# dashboard.net
KiCad netlist of a schematic drawn in EAGLE
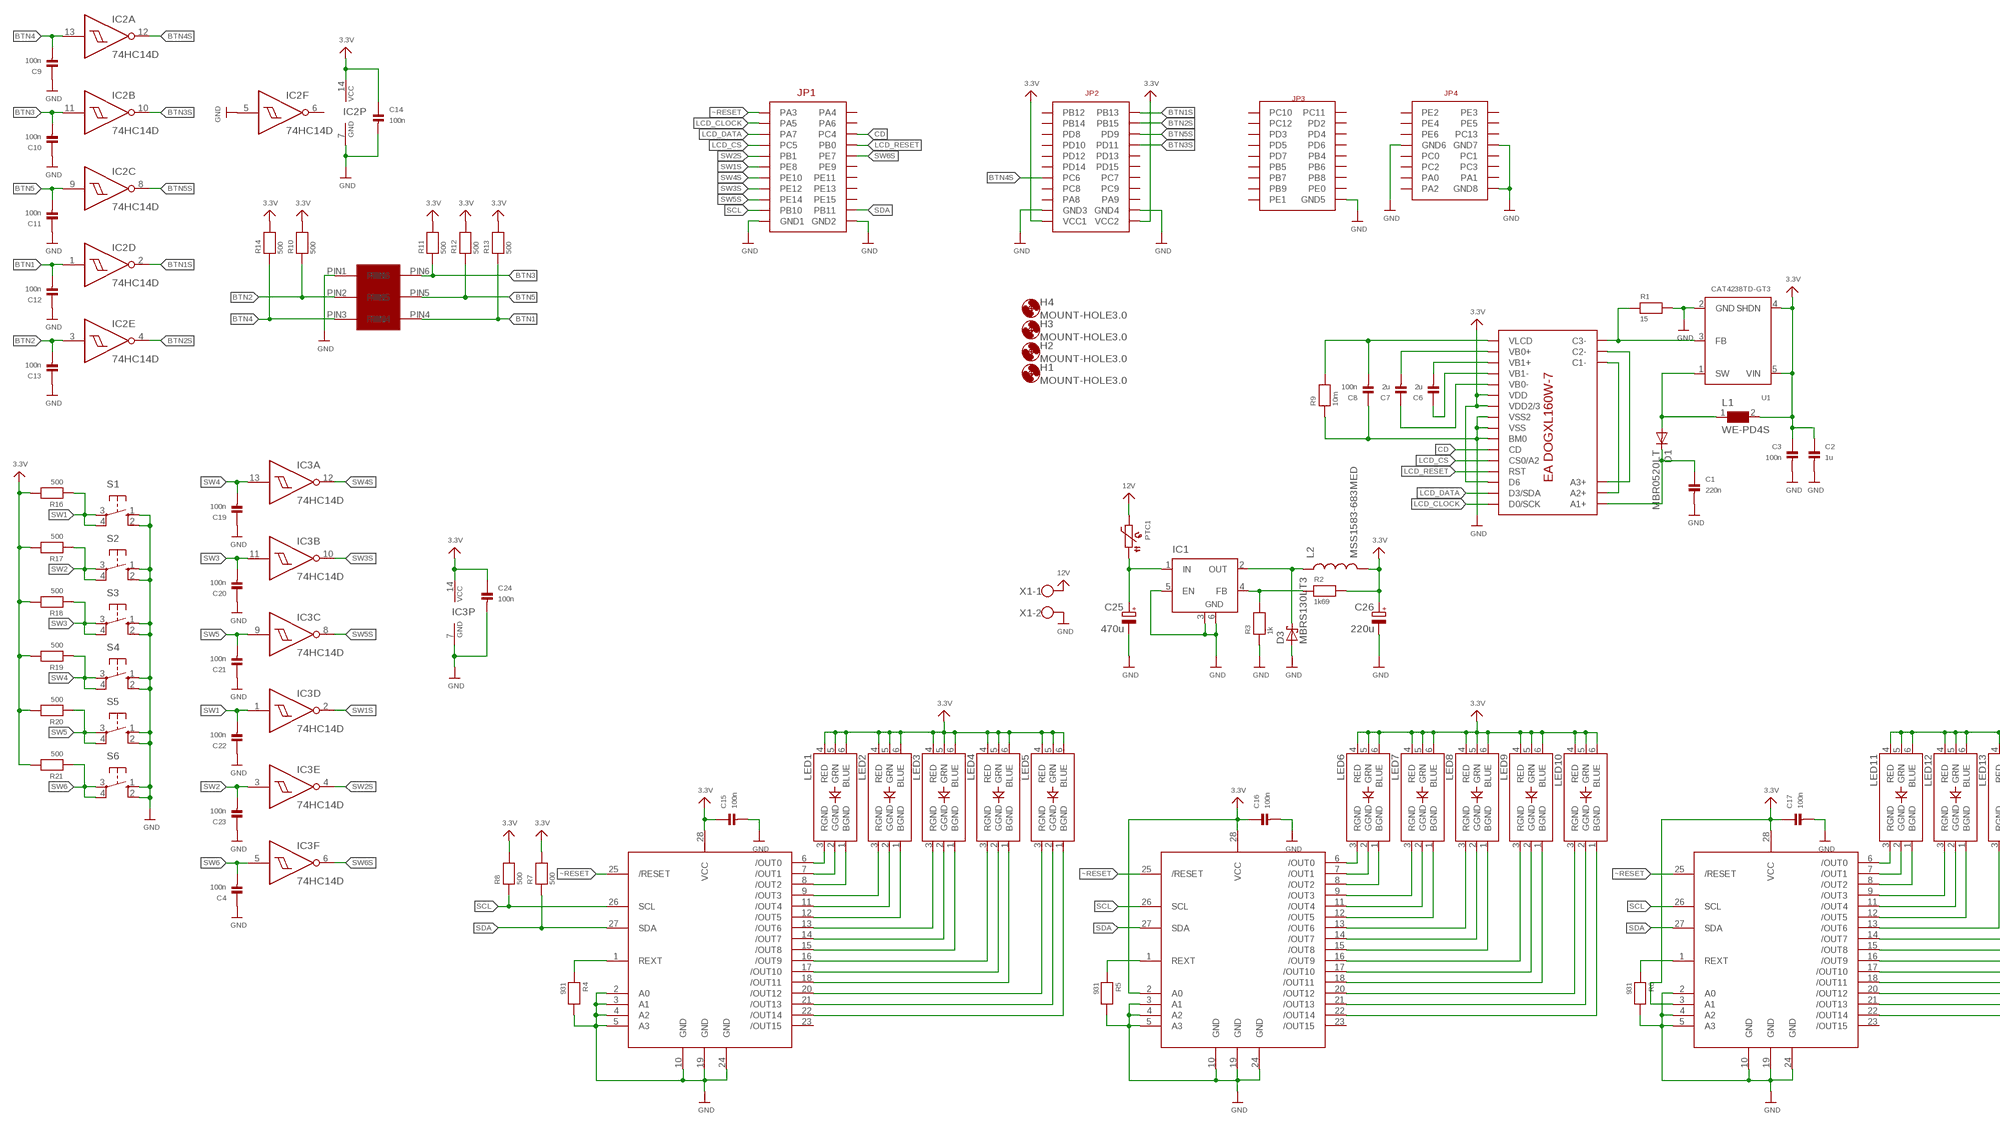
[diagram p0: schematic, sheet 1, part 1 of 2]
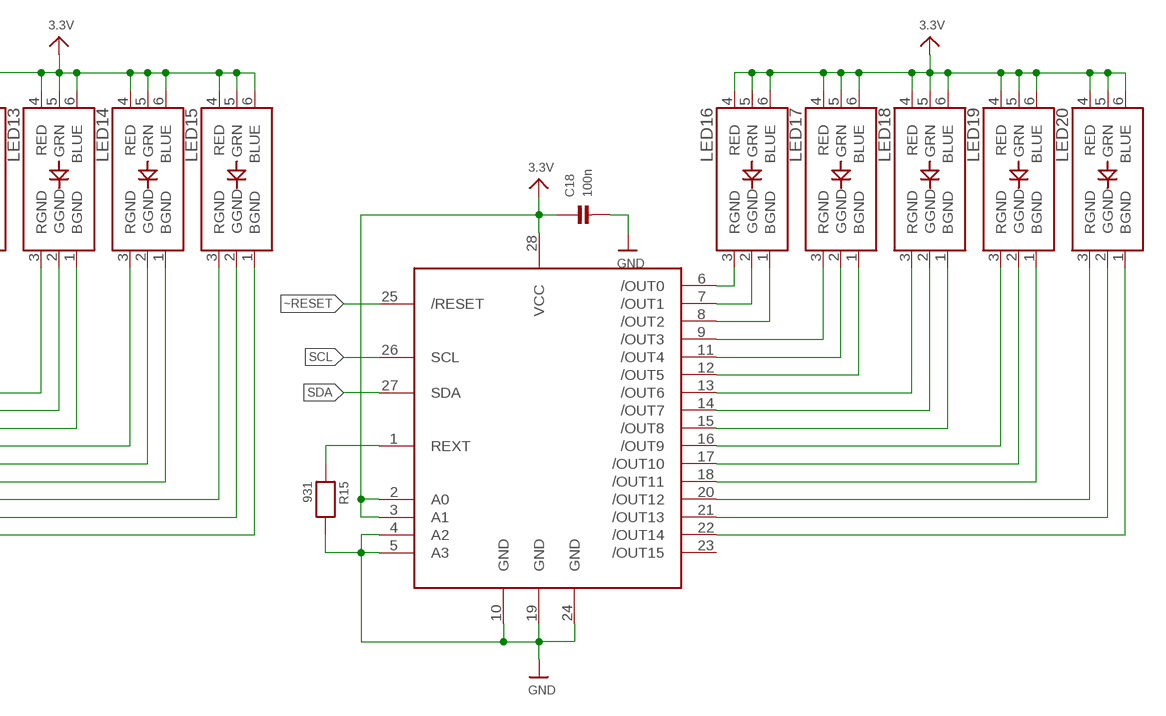
[diagram p1: schematic, sheet 1, part 2 of 2]

(export (version "E")
  (design (tool "Eeschema 10.0.6"))
  (components
    (comp (ref "C1")
      (value "220n")
      (footprint "eagle-import:_0805")
      (libsource (lib "eagle-import") (part "CAP_CERAMIC_0805"))
    )
    (comp (ref "C2")
      (value "1u")
      (footprint "eagle-import:_0805")
      (libsource (lib "eagle-import") (part "CAP_CERAMIC_0805"))
    )
    (comp (ref "C3")
      (value "100n")
      (footprint "eagle-import:_0603")
      (libsource (lib "eagle-import") (part "CAP_CERAMIC_0603"))
    )
    (comp (ref "C4")
      (value "100n")
      (footprint "eagle-import:_0603")
      (libsource (lib "eagle-import") (part "CAP_CERAMIC_0603"))
    )
    (comp (ref "C6")
      (value "2u")
      (footprint "eagle-import:_0805")
      (libsource (lib "eagle-import") (part "CAP_CERAMIC_0805"))
    )
    (comp (ref "C7")
      (value "2u")
      (footprint "eagle-import:_0805")
      (libsource (lib "eagle-import") (part "CAP_CERAMIC_0805"))
    )
    (comp (ref "C8")
      (value "100n")
      (footprint "eagle-import:_0603")
      (libsource (lib "eagle-import") (part "CAP_CERAMIC_0603"))
    )
    (comp (ref "C9")
      (value "100n")
      (footprint "eagle-import:_0603")
      (libsource (lib "eagle-import") (part "CAP_CERAMIC_0603"))
    )
    (comp (ref "C10")
      (value "100n")
      (footprint "eagle-import:_0603")
      (libsource (lib "eagle-import") (part "CAP_CERAMIC_0603"))
    )
    (comp (ref "C11")
      (value "100n")
      (footprint "eagle-import:_0603")
      (libsource (lib "eagle-import") (part "CAP_CERAMIC_0603"))
    )
    (comp (ref "C12")
      (value "100n")
      (footprint "eagle-import:_0603")
      (libsource (lib "eagle-import") (part "CAP_CERAMIC_0603"))
    )
    (comp (ref "C13")
      (value "100n")
      (footprint "eagle-import:_0603")
      (libsource (lib "eagle-import") (part "CAP_CERAMIC_0603"))
    )
    (comp (ref "C14")
      (value "100n")
      (footprint "eagle-import:_0603")
      (libsource (lib "eagle-import") (part "CAP_CERAMIC_0603"))
    )
    (comp (ref "C15")
      (value "100n")
      (footprint "eagle-import:_0603")
      (libsource (lib "eagle-import") (part "CAP_CERAMIC_0603"))
    )
    (comp (ref "C16")
      (value "100n")
      (footprint "eagle-import:_0603")
      (libsource (lib "eagle-import") (part "CAP_CERAMIC_0603"))
    )
    (comp (ref "C17")
      (value "100n")
      (footprint "eagle-import:_0603")
      (libsource (lib "eagle-import") (part "CAP_CERAMIC_0603"))
    )
    (comp (ref "C18")
      (value "100n")
      (footprint "eagle-import:_0603")
      (libsource (lib "eagle-import") (part "CAP_CERAMIC_0603"))
    )
    (comp (ref "C19")
      (value "100n")
      (footprint "eagle-import:_0603")
      (libsource (lib "eagle-import") (part "CAP_CERAMIC_0603"))
    )
    (comp (ref "C20")
      (value "100n")
      (footprint "eagle-import:_0603")
      (libsource (lib "eagle-import") (part "CAP_CERAMIC_0603"))
    )
    (comp (ref "C21")
      (value "100n")
      (footprint "eagle-import:_0603")
      (libsource (lib "eagle-import") (part "CAP_CERAMIC_0603"))
    )
    (comp (ref "C22")
      (value "100n")
      (footprint "eagle-import:_0603")
      (libsource (lib "eagle-import") (part "CAP_CERAMIC_0603"))
    )
    (comp (ref "C23")
      (value "100n")
      (footprint "eagle-import:_0603")
      (libsource (lib "eagle-import") (part "CAP_CERAMIC_0603"))
    )
    (comp (ref "C24")
      (value "100n")
      (footprint "eagle-import:_0603")
      (libsource (lib "eagle-import") (part "CAP_CERAMIC_0603"))
    )
    (comp (ref "C25")
      (value "470u")
      (footprint "eagle-import:153CLV-1012")
      (libsource (lib "eagle-import") (part "CPOL-EU153CLV-1012"))
    )
    (comp (ref "C26")
      (value "220u")
      (footprint "eagle-import:153CLV-1012")
      (libsource (lib "eagle-import") (part "CPOL-EU153CLV-1012"))
    )
    (comp (ref "D1")
      (value "MBR0520LT")
      (footprint "eagle-import:SOD123")
      (libsource (lib "eagle-import") (part "MBR0520LT"))
    )
    (comp (ref "D3")
      (value "MBRS130LT3")
      (footprint "eagle-import:SMB")
      (libsource (lib "eagle-import") (part "MBRS130LT3"))
    )
    (comp (ref "H1")
      (value "MOUNT-HOLE3.0")
      (footprint "eagle-import:3,0")
      (libsource (lib "eagle-import") (part "MOUNT-HOLE3.0"))
    )
    (comp (ref "H2")
      (value "MOUNT-HOLE3.0")
      (footprint "eagle-import:3,0")
      (libsource (lib "eagle-import") (part "MOUNT-HOLE3.0"))
    )
    (comp (ref "H3")
      (value "MOUNT-HOLE3.0")
      (footprint "eagle-import:3,0")
      (libsource (lib "eagle-import") (part "MOUNT-HOLE3.0"))
    )
    (comp (ref "H4")
      (value "MOUNT-HOLE3.0")
      (footprint "eagle-import:3,0")
      (libsource (lib "eagle-import") (part "MOUNT-HOLE3.0"))
    )
    (comp (ref "IC1")
      (value "LM2596S")
      (footprint "eagle-import:TO263-5")
      (libsource (lib "eagle-import") (part "LM2596S"))
    )
    (comp (ref "IC2")
      (value "74HC14D")
      (footprint "eagle-import:SO14")
      (libsource (lib "eagle-import") (part "7414DHC"))
    )
    (comp (ref "IC3")
      (value "74HC14D")
      (footprint "eagle-import:SO14")
      (libsource (lib "eagle-import") (part "7414DHC"))
    )
    (comp (ref "L1")
      (value "WE-PD4S")
      (footprint "eagle-import:S")
      (fields (field (name "MPN") "7445501"))
      (libsource (lib "eagle-import") (part "WE-PD4_S-7445501"))
    )
    (comp (ref "L2")
      (value "MSS1583-683MED")
      (footprint "eagle-import:CDRH125")
      (libsource (lib "eagle-import") (part "INDUCTORPWR"))
    )
    (comp (ref "LED1")
      (value "LED_RGB_PLCC6CREE-CLV6A")
      (footprint "eagle-import:RGBLED_PLCC6")
      (libsource (lib "eagle-import") (part "LED_RGB_PLCC6CREE-CLV6A"))
    )
    (comp (ref "LED2")
      (value "LED_RGB_PLCC6CREE-CLV6A")
      (footprint "eagle-import:RGBLED_PLCC6")
      (libsource (lib "eagle-import") (part "LED_RGB_PLCC6CREE-CLV6A"))
    )
    (comp (ref "LED3")
      (value "LED_RGB_PLCC6CREE-CLV6A")
      (footprint "eagle-import:RGBLED_PLCC6")
      (libsource (lib "eagle-import") (part "LED_RGB_PLCC6CREE-CLV6A"))
    )
    (comp (ref "LED4")
      (value "LED_RGB_PLCC6CREE-CLV6A")
      (footprint "eagle-import:RGBLED_PLCC6")
      (libsource (lib "eagle-import") (part "LED_RGB_PLCC6CREE-CLV6A"))
    )
    (comp (ref "LED5")
      (value "LED_RGB_PLCC6CREE-CLV6A")
      (footprint "eagle-import:RGBLED_PLCC6")
      (libsource (lib "eagle-import") (part "LED_RGB_PLCC6CREE-CLV6A"))
    )
    (comp (ref "LED6")
      (value "LED_RGB_PLCC6CREE-CLV6A")
      (footprint "eagle-import:RGBLED_PLCC6")
      (libsource (lib "eagle-import") (part "LED_RGB_PLCC6CREE-CLV6A"))
    )
    (comp (ref "LED7")
      (value "LED_RGB_PLCC6CREE-CLV6A")
      (footprint "eagle-import:RGBLED_PLCC6")
      (libsource (lib "eagle-import") (part "LED_RGB_PLCC6CREE-CLV6A"))
    )
    (comp (ref "LED8")
      (value "LED_RGB_PLCC6CREE-CLV6A")
      (footprint "eagle-import:RGBLED_PLCC6")
      (libsource (lib "eagle-import") (part "LED_RGB_PLCC6CREE-CLV6A"))
    )
    (comp (ref "LED9")
      (value "LED_RGB_PLCC6CREE-CLV6A")
      (footprint "eagle-import:RGBLED_PLCC6")
      (libsource (lib "eagle-import") (part "LED_RGB_PLCC6CREE-CLV6A"))
    )
    (comp (ref "LED10")
      (value "LED_RGB_PLCC6CREE-CLV6A")
      (footprint "eagle-import:RGBLED_PLCC6")
      (libsource (lib "eagle-import") (part "LED_RGB_PLCC6CREE-CLV6A"))
    )
    (comp (ref "LED11")
      (value "LED_RGB_PLCC6CREE-CLV6A")
      (footprint "eagle-import:RGBLED_PLCC6")
      (libsource (lib "eagle-import") (part "LED_RGB_PLCC6CREE-CLV6A"))
    )
    (comp (ref "LED12")
      (value "LED_RGB_PLCC6CREE-CLV6A")
      (footprint "eagle-import:RGBLED_PLCC6")
      (libsource (lib "eagle-import") (part "LED_RGB_PLCC6CREE-CLV6A"))
    )
    (comp (ref "LED13")
      (value "LED_RGB_PLCC6CREE-CLV6A")
      (footprint "eagle-import:RGBLED_PLCC6")
      (libsource (lib "eagle-import") (part "LED_RGB_PLCC6CREE-CLV6A"))
    )
    (comp (ref "LED14")
      (value "LED_RGB_PLCC6CREE-CLV6A")
      (footprint "eagle-import:RGBLED_PLCC6")
      (libsource (lib "eagle-import") (part "LED_RGB_PLCC6CREE-CLV6A"))
    )
    (comp (ref "LED15")
      (value "LED_RGB_PLCC6CREE-CLV6A")
      (footprint "eagle-import:RGBLED_PLCC6")
      (libsource (lib "eagle-import") (part "LED_RGB_PLCC6CREE-CLV6A"))
    )
    (comp (ref "LED16")
      (value "LED_RGB_PLCC6CREE-CLV6A")
      (footprint "eagle-import:RGBLED_PLCC6")
      (libsource (lib "eagle-import") (part "LED_RGB_PLCC6CREE-CLV6A"))
    )
    (comp (ref "LED17")
      (value "LED_RGB_PLCC6CREE-CLV6A")
      (footprint "eagle-import:RGBLED_PLCC6")
      (libsource (lib "eagle-import") (part "LED_RGB_PLCC6CREE-CLV6A"))
    )
    (comp (ref "LED18")
      (value "LED_RGB_PLCC6CREE-CLV6A")
      (footprint "eagle-import:RGBLED_PLCC6")
      (libsource (lib "eagle-import") (part "LED_RGB_PLCC6CREE-CLV6A"))
    )
    (comp (ref "LED19")
      (value "LED_RGB_PLCC6CREE-CLV6A")
      (footprint "eagle-import:RGBLED_PLCC6")
      (libsource (lib "eagle-import") (part "LED_RGB_PLCC6CREE-CLV6A"))
    )
    (comp (ref "LED20")
      (value "LED_RGB_PLCC6CREE-CLV6A")
      (footprint "eagle-import:RGBLED_PLCC6")
      (libsource (lib "eagle-import") (part "LED_RGB_PLCC6CREE-CLV6A"))
    )
    (comp (ref "PTC1")
      (value "PTC1812")
      (footprint "eagle-import:PTC1812")
      (libsource (lib "eagle-import") (part "PTC1812"))
    )
    (comp (ref "R1")
      (value "15")
      (footprint "eagle-import:_0603")
      (libsource (lib "eagle-import") (part "RESISTOR_0603"))
    )
    (comp (ref "R2")
      (value "1k69")
      (footprint "eagle-import:_0603")
      (libsource (lib "eagle-import") (part "RESISTOR_0603"))
    )
    (comp (ref "R3")
      (value "1k")
      (footprint "eagle-import:_0603")
      (libsource (lib "eagle-import") (part "RESISTOR_0603"))
    )
    (comp (ref "R4")
      (value "931")
      (footprint "eagle-import:_0603")
      (libsource (lib "eagle-import") (part "RESISTOR_0603"))
    )
    (comp (ref "R5")
      (value "931")
      (footprint "eagle-import:_0603")
      (libsource (lib "eagle-import") (part "RESISTOR_0603"))
    )
    (comp (ref "R6")
      (value "931")
      (footprint "eagle-import:_0603")
      (libsource (lib "eagle-import") (part "RESISTOR_0603"))
    )
    (comp (ref "R7")
      (value "500")
      (footprint "eagle-import:_0603")
      (libsource (lib "eagle-import") (part "RESISTOR_0603"))
    )
    (comp (ref "R8")
      (value "500")
      (footprint "eagle-import:_0603")
      (libsource (lib "eagle-import") (part "RESISTOR_0603"))
    )
    (comp (ref "R9")
      (value "10m")
      (footprint "eagle-import:_0805")
      (libsource (lib "eagle-import") (part "RESISTOR_0805"))
    )
    (comp (ref "R10")
      (value "500")
      (footprint "eagle-import:_0603")
      (libsource (lib "eagle-import") (part "RESISTOR_0603"))
    )
    (comp (ref "R11")
      (value "500")
      (footprint "eagle-import:_0603")
      (libsource (lib "eagle-import") (part "RESISTOR_0603"))
    )
    (comp (ref "R12")
      (value "500")
      (footprint "eagle-import:_0603")
      (libsource (lib "eagle-import") (part "RESISTOR_0603"))
    )
    (comp (ref "R13")
      (value "500")
      (footprint "eagle-import:_0603")
      (libsource (lib "eagle-import") (part "RESISTOR_0603"))
    )
    (comp (ref "R14")
      (value "500")
      (footprint "eagle-import:_0603")
      (libsource (lib "eagle-import") (part "RESISTOR_0603"))
    )
    (comp (ref "R15")
      (value "931")
      (footprint "eagle-import:_0603")
      (libsource (lib "eagle-import") (part "RESISTOR_0603"))
    )
    (comp (ref "R16")
      (value "500")
      (footprint "eagle-import:_0603")
      (libsource (lib "eagle-import") (part "RESISTOR_0603"))
    )
    (comp (ref "R17")
      (value "500")
      (footprint "eagle-import:_0603")
      (libsource (lib "eagle-import") (part "RESISTOR_0603"))
    )
    (comp (ref "R18")
      (value "500")
      (footprint "eagle-import:_0603")
      (libsource (lib "eagle-import") (part "RESISTOR_0603"))
    )
    (comp (ref "R19")
      (value "500")
      (footprint "eagle-import:_0603")
      (libsource (lib "eagle-import") (part "RESISTOR_0603"))
    )
    (comp (ref "R20")
      (value "500")
      (footprint "eagle-import:_0603")
      (libsource (lib "eagle-import") (part "RESISTOR_0603"))
    )
    (comp (ref "R21")
      (value "500")
      (footprint "eagle-import:_0603")
      (libsource (lib "eagle-import") (part "RESISTOR_0603"))
    )
    (comp (ref "S1")
      (value "10-XX")
      (footprint "eagle-import:B3F-10XX")
      (fields (field (name "MPN") "B3F-1000"))
      (libsource (lib "eagle-import") (part "10-XX"))
    )
    (comp (ref "S2")
      (value "10-XX")
      (footprint "eagle-import:B3F-10XX")
      (fields (field (name "MPN") "B3F-1000"))
      (libsource (lib "eagle-import") (part "10-XX"))
    )
    (comp (ref "S3")
      (value "10-XX")
      (footprint "eagle-import:B3F-10XX")
      (fields (field (name "MPN") "B3F-1000"))
      (libsource (lib "eagle-import") (part "10-XX"))
    )
    (comp (ref "S4")
      (value "10-XX")
      (footprint "eagle-import:B3F-10XX")
      (fields (field (name "MPN") "B3F-1000"))
      (libsource (lib "eagle-import") (part "10-XX"))
    )
    (comp (ref "S5")
      (value "10-XX")
      (footprint "eagle-import:B3F-10XX")
      (fields
        (field (name "MPN") "B3F-1000")
        (field (name "MPN_1") "B3F-1000")
        (field (name "OC_FARNELL") "176432")
        (field (name "OC_NEWARK") "36M3542")
      )
      (libsource (lib "eagle-import") (part "10-XX"))
    )
    (comp (ref "S6")
      (value "10-XX")
      (footprint "eagle-import:B3F-10XX")
      (fields
        (field (name "MPN") "B3F-1000")
        (field (name "MPN_1") "B3F-1000")
        (field (name "OC_FARNELL") "176432")
        (field (name "OC_NEWARK") "36M3542")
      )
      (libsource (lib "eagle-import") (part "10-XX"))
    )
    (comp (ref "U$1")
      (value "CPU-BOARD")
      (footprint "eagle-import:CPU-BOARD-JP1")
      (libsource (lib "eagle-import") (part "CPU-BOARD"))
    )
    (comp (ref "U$10")
      (value "EA-DOGXL160W-7")
      (footprint "eagle-import:EA-DOGXL160W-7")
      (libsource (lib "eagle-import") (part "EA-DOGXL160W-7"))
    )
    (comp (ref "U$30")
      (value "TLC59116")
      (footprint "eagle-import:TSSOP28")
      (libsource (lib "eagle-import") (part "TLC59116"))
    )
    (comp (ref "U$33")
      (value "TLC59116")
      (footprint "eagle-import:TSSOP28")
      (libsource (lib "eagle-import") (part "TLC59116"))
    )
    (comp (ref "U$36")
      (value "TLC59116")
      (footprint "eagle-import:TSSOP28")
      (libsource (lib "eagle-import") (part "TLC59116"))
    )
    (comp (ref "U$42")
      (value "MICROFIT6")
      (footprint "eagle-import:MICROFIT6SOCK")
      (libsource (lib "eagle-import") (part "MICROFIT6"))
    )
    (comp (ref "U$51")
      (value "TLC59116")
      (footprint "eagle-import:TSSOP28")
      (libsource (lib "eagle-import") (part "TLC59116"))
    )
    (comp (ref "U1")
      (value "CAT4238TD-GT3")
      (footprint "eagle-import:SOT23-5")
      (libsource (lib "eagle-import") (part "FAN5331"))
    )
    (comp (ref "X1")
      (value "W237-102")
      (footprint "eagle-import:W237-102")
      (fields (field (name "MPN") "237-102"))
      (libsource (lib "eagle-import") (part "W237-102"))
    )
  )
  (nets
    (net (code "1") (name "/~{RESET}") (class "Default")
      (node (ref "U$1") (pin "P$1") (pinfunction "PA3_P$1") (pintype "bidirectional"))
      (node (ref "U$30") (pin "25") (pinfunction "/RESET_25") (pintype "bidirectional"))
      (node (ref "U$33") (pin "25") (pinfunction "/RESET_25") (pintype "bidirectional"))
      (node (ref "U$36") (pin "25") (pinfunction "/RESET_25") (pintype "bidirectional"))
      (node (ref "U$51") (pin "25") (pinfunction "/RESET_25") (pintype "bidirectional"))
    )
    (net (code "2") (name "3.3V") (class "Default")
      (node (ref "C14") (pin "1") (pinfunction "P$1_1") (pintype "passive"))
      (node (ref "C15") (pin "1") (pinfunction "P$1_1") (pintype "passive"))
      (node (ref "C16") (pin "1") (pinfunction "P$1_1") (pintype "passive"))
      (node (ref "C17") (pin "1") (pinfunction "P$1_1") (pintype "passive"))
      (node (ref "C18") (pin "1") (pinfunction "P$1_1") (pintype "passive"))
      (node (ref "C2") (pin "1") (pinfunction "P$1_1") (pintype "passive"))
      (node (ref "C24") (pin "1") (pinfunction "P$1_1") (pintype "passive"))
      (node (ref "C26") (pin "+") (pinfunction "+_+") (pintype "passive"))
      (node (ref "C3") (pin "1") (pinfunction "P$1_1") (pintype "passive"))
      (node (ref "IC2") (pin "14") (pinfunction "VCC_14") (pintype "power_in"))
      (node (ref "IC3") (pin "14") (pinfunction "VCC_14") (pintype "power_in"))
      (node (ref "L1") (pin "2") (pinfunction "2_2") (pintype "passive"))
      (node (ref "L2") (pin "2") (pinfunction "2_2") (pintype "passive"))
      (node (ref "LED1") (pin "4") (pinfunction "RED_4") (pintype "bidirectional"))
      (node (ref "LED1") (pin "5") (pinfunction "GRN_5") (pintype "bidirectional"))
      (node (ref "LED1") (pin "6") (pinfunction "BLUE_6") (pintype "bidirectional"))
      (node (ref "LED10") (pin "4") (pinfunction "RED_4") (pintype "bidirectional"))
      (node (ref "LED10") (pin "5") (pinfunction "GRN_5") (pintype "bidirectional"))
      (node (ref "LED10") (pin "6") (pinfunction "BLUE_6") (pintype "bidirectional"))
      (node (ref "LED11") (pin "4") (pinfunction "RED_4") (pintype "bidirectional"))
      (node (ref "LED11") (pin "5") (pinfunction "GRN_5") (pintype "bidirectional"))
      (node (ref "LED11") (pin "6") (pinfunction "BLUE_6") (pintype "bidirectional"))
      (node (ref "LED12") (pin "4") (pinfunction "RED_4") (pintype "bidirectional"))
      (node (ref "LED12") (pin "5") (pinfunction "GRN_5") (pintype "bidirectional"))
      (node (ref "LED12") (pin "6") (pinfunction "BLUE_6") (pintype "bidirectional"))
      (node (ref "LED13") (pin "4") (pinfunction "RED_4") (pintype "bidirectional"))
      (node (ref "LED13") (pin "5") (pinfunction "GRN_5") (pintype "bidirectional"))
      (node (ref "LED13") (pin "6") (pinfunction "BLUE_6") (pintype "bidirectional"))
      (node (ref "LED14") (pin "4") (pinfunction "RED_4") (pintype "bidirectional"))
      (node (ref "LED14") (pin "5") (pinfunction "GRN_5") (pintype "bidirectional"))
      (node (ref "LED14") (pin "6") (pinfunction "BLUE_6") (pintype "bidirectional"))
      (node (ref "LED15") (pin "4") (pinfunction "RED_4") (pintype "bidirectional"))
      (node (ref "LED15") (pin "5") (pinfunction "GRN_5") (pintype "bidirectional"))
      (node (ref "LED15") (pin "6") (pinfunction "BLUE_6") (pintype "bidirectional"))
      (node (ref "LED16") (pin "4") (pinfunction "RED_4") (pintype "bidirectional"))
      (node (ref "LED16") (pin "5") (pinfunction "GRN_5") (pintype "bidirectional"))
      (node (ref "LED16") (pin "6") (pinfunction "BLUE_6") (pintype "bidirectional"))
      (node (ref "LED17") (pin "4") (pinfunction "RED_4") (pintype "bidirectional"))
      (node (ref "LED17") (pin "5") (pinfunction "GRN_5") (pintype "bidirectional"))
      (node (ref "LED17") (pin "6") (pinfunction "BLUE_6") (pintype "bidirectional"))
      (node (ref "LED18") (pin "4") (pinfunction "RED_4") (pintype "bidirectional"))
      (node (ref "LED18") (pin "5") (pinfunction "GRN_5") (pintype "bidirectional"))
      (node (ref "LED18") (pin "6") (pinfunction "BLUE_6") (pintype "bidirectional"))
      (node (ref "LED19") (pin "4") (pinfunction "RED_4") (pintype "bidirectional"))
      (node (ref "LED19") (pin "5") (pinfunction "GRN_5") (pintype "bidirectional"))
      (node (ref "LED19") (pin "6") (pinfunction "BLUE_6") (pintype "bidirectional"))
      (node (ref "LED2") (pin "4") (pinfunction "RED_4") (pintype "bidirectional"))
      (node (ref "LED2") (pin "5") (pinfunction "GRN_5") (pintype "bidirectional"))
      (node (ref "LED2") (pin "6") (pinfunction "BLUE_6") (pintype "bidirectional"))
      (node (ref "LED20") (pin "4") (pinfunction "RED_4") (pintype "bidirectional"))
      (node (ref "LED20") (pin "5") (pinfunction "GRN_5") (pintype "bidirectional"))
      (node (ref "LED20") (pin "6") (pinfunction "BLUE_6") (pintype "bidirectional"))
      (node (ref "LED3") (pin "4") (pinfunction "RED_4") (pintype "bidirectional"))
      (node (ref "LED3") (pin "5") (pinfunction "GRN_5") (pintype "bidirectional"))
      (node (ref "LED3") (pin "6") (pinfunction "BLUE_6") (pintype "bidirectional"))
      (node (ref "LED4") (pin "4") (pinfunction "RED_4") (pintype "bidirectional"))
      (node (ref "LED4") (pin "5") (pinfunction "GRN_5") (pintype "bidirectional"))
      (node (ref "LED4") (pin "6") (pinfunction "BLUE_6") (pintype "bidirectional"))
      (node (ref "LED5") (pin "4") (pinfunction "RED_4") (pintype "bidirectional"))
      (node (ref "LED5") (pin "5") (pinfunction "GRN_5") (pintype "bidirectional"))
      (node (ref "LED5") (pin "6") (pinfunction "BLUE_6") (pintype "bidirectional"))
      (node (ref "LED6") (pin "4") (pinfunction "RED_4") (pintype "bidirectional"))
      (node (ref "LED6") (pin "5") (pinfunction "GRN_5") (pintype "bidirectional"))
      (node (ref "LED6") (pin "6") (pinfunction "BLUE_6") (pintype "bidirectional"))
      (node (ref "LED7") (pin "4") (pinfunction "RED_4") (pintype "bidirectional"))
      (node (ref "LED7") (pin "5") (pinfunction "GRN_5") (pintype "bidirectional"))
      (node (ref "LED7") (pin "6") (pinfunction "BLUE_6") (pintype "bidirectional"))
      (node (ref "LED8") (pin "4") (pinfunction "RED_4") (pintype "bidirectional"))
      (node (ref "LED8") (pin "5") (pinfunction "GRN_5") (pintype "bidirectional"))
      (node (ref "LED8") (pin "6") (pinfunction "BLUE_6") (pintype "bidirectional"))
      (node (ref "LED9") (pin "4") (pinfunction "RED_4") (pintype "bidirectional"))
      (node (ref "LED9") (pin "5") (pinfunction "GRN_5") (pintype "bidirectional"))
      (node (ref "LED9") (pin "6") (pinfunction "BLUE_6") (pintype "bidirectional"))
      (node (ref "R10") (pin "2") (pinfunction "2_2") (pintype "passive"))
      (node (ref "R11") (pin "2") (pinfunction "2_2") (pintype "passive"))
      (node (ref "R12") (pin "2") (pinfunction "2_2") (pintype "passive"))
      (node (ref "R13") (pin "2") (pinfunction "2_2") (pintype "passive"))
      (node (ref "R14") (pin "2") (pinfunction "2_2") (pintype "passive"))
      (node (ref "R16") (pin "2") (pinfunction "2_2") (pintype "passive"))
      (node (ref "R17") (pin "2") (pinfunction "2_2") (pintype "passive"))
      (node (ref "R18") (pin "2") (pinfunction "2_2") (pintype "passive"))
      (node (ref "R19") (pin "2") (pinfunction "2_2") (pintype "passive"))
      (node (ref "R2") (pin "2") (pinfunction "2_2") (pintype "passive"))
      (node (ref "R20") (pin "2") (pinfunction "2_2") (pintype "passive"))
      (node (ref "R21") (pin "2") (pinfunction "2_2") (pintype "passive"))
      (node (ref "R7") (pin "2") (pinfunction "2_2") (pintype "passive"))
      (node (ref "R8") (pin "2") (pinfunction "2_2") (pintype "passive"))
      (node (ref "U$1") (pin "P$43") (pinfunction "VCC1_P$43") (pintype "bidirectional"))
      (node (ref "U$1") (pin "P$44") (pinfunction "VCC2_P$44") (pintype "bidirectional"))
      (node (ref "U$10") (pin "P$22") (pinfunction "VDD_P$22") (pintype "bidirectional"))
      (node (ref "U$10") (pin "P$23") (pinfunction "VDD2/3_P$23") (pintype "bidirectional"))
      (node (ref "U$10") (pin "P$30") (pinfunction "D6_P$30") (pintype "bidirectional"))
      (node (ref "U$30") (pin "28") (pinfunction "VCC_28") (pintype "bidirectional"))
      (node (ref "U$33") (pin "2") (pinfunction "A0_2") (pintype "bidirectional"))
      (node (ref "U$33") (pin "28") (pinfunction "VCC_28") (pintype "bidirectional"))
      (node (ref "U$36") (pin "28") (pinfunction "VCC_28") (pintype "bidirectional"))
      (node (ref "U$36") (pin "3") (pinfunction "A1_3") (pintype "bidirectional"))
      (node (ref "U$51") (pin "2") (pinfunction "A0_2") (pintype "bidirectional"))
      (node (ref "U$51") (pin "28") (pinfunction "VCC_28") (pintype "bidirectional"))
      (node (ref "U$51") (pin "3") (pinfunction "A1_3") (pintype "bidirectional"))
      (node (ref "U1") (pin "4") (pinfunction "SHDN_4") (pintype "bidirectional"))
      (node (ref "U1") (pin "5") (pinfunction "VIN_5") (pintype "bidirectional"))
    )
    (net (code "3") (name "12V") (class "Default")
      (node (ref "PTC1") (pin "P$2") (pinfunction "2_P$2") (pintype "passive"))
      (node (ref "X1") (pin "1") (pinfunction "KL_1") (pintype "passive"))
    )
    (net (code "4") (name "BTN1") (class "Default")
      (node (ref "C12") (pin "2") (pinfunction "P$2_2") (pintype "passive"))
      (node (ref "IC2") (pin "1") (pinfunction "I_1") (pintype "input"))
      (node (ref "R13") (pin "1") (pinfunction "1_1") (pintype "passive"))
      (node (ref "U$42") (pin "PIN4") (pinfunction "PIN4_PIN4") (pintype "bidirectional"))
    )
    (net (code "5") (name "BTN1S") (class "Default")
      (node (ref "IC2") (pin "2") (pinfunction "O_2") (pintype "output"))
      (node (ref "U$1") (pin "P$24") (pinfunction "PB13_P$24") (pintype "bidirectional"))
    )
    (net (code "6") (name "BTN2") (class "Default")
      (node (ref "C13") (pin "2") (pinfunction "P$2_2") (pintype "passive"))
      (node (ref "IC2") (pin "3") (pinfunction "I_3") (pintype "input"))
      (node (ref "R10") (pin "1") (pinfunction "1_1") (pintype "passive"))
      (node (ref "U$42") (pin "PIN2") (pinfunction "PIN2_PIN2") (pintype "bidirectional"))
    )
    (net (code "7") (name "BTN2S") (class "Default")
      (node (ref "IC2") (pin "4") (pinfunction "O_4") (pintype "output"))
      (node (ref "U$1") (pin "P$26") (pinfunction "PB15_P$26") (pintype "bidirectional"))
    )
    (net (code "8") (name "BTN3") (class "Default")
      (node (ref "C10") (pin "2") (pinfunction "P$2_2") (pintype "passive"))
      (node (ref "IC2") (pin "11") (pinfunction "I_11") (pintype "input"))
      (node (ref "R11") (pin "1") (pinfunction "1_1") (pintype "passive"))
      (node (ref "U$42") (pin "PIN6") (pinfunction "PIN6_PIN6") (pintype "bidirectional"))
    )
    (net (code "9") (name "BTN3S") (class "Default")
      (node (ref "IC2") (pin "10") (pinfunction "O_10") (pintype "output"))
      (node (ref "U$1") (pin "P$30") (pinfunction "PD11_P$30") (pintype "bidirectional"))
    )
    (net (code "10") (name "BTN4") (class "Default")
      (node (ref "C9") (pin "2") (pinfunction "P$2_2") (pintype "passive"))
      (node (ref "IC2") (pin "13") (pinfunction "I_13") (pintype "input"))
      (node (ref "R14") (pin "1") (pinfunction "1_1") (pintype "passive"))
      (node (ref "U$42") (pin "PIN3") (pinfunction "PIN3_PIN3") (pintype "bidirectional"))
    )
    (net (code "11") (name "BTN4S") (class "Default")
      (node (ref "IC2") (pin "12") (pinfunction "O_12") (pintype "output"))
      (node (ref "U$1") (pin "P$35") (pinfunction "PC6_P$35") (pintype "bidirectional"))
    )
    (net (code "12") (name "BTN5") (class "Default")
      (node (ref "C11") (pin "2") (pinfunction "P$2_2") (pintype "passive"))
      (node (ref "IC2") (pin "9") (pinfunction "I_9") (pintype "input"))
      (node (ref "R12") (pin "1") (pinfunction "1_1") (pintype "passive"))
      (node (ref "U$42") (pin "PIN5") (pinfunction "PIN5_PIN5") (pintype "bidirectional"))
    )
    (net (code "13") (name "BTN5S") (class "Default")
      (node (ref "IC2") (pin "8") (pinfunction "O_8") (pintype "output"))
      (node (ref "U$1") (pin "P$28") (pinfunction "PD9_P$28") (pintype "bidirectional"))
    )
    (net (code "14") (name "CD") (class "Default")
      (node (ref "U$1") (pin "P$6") (pinfunction "PC4_P$6") (pintype "bidirectional"))
      (node (ref "U$10") (pin "P$27") (pinfunction "CD_P$27") (pintype "bidirectional"))
    )
    (net (code "15") (name "GND") (class "Default")
      (node (ref "C1") (pin "2") (pinfunction "P$2_2") (pintype "passive"))
      (node (ref "C10") (pin "1") (pinfunction "P$1_1") (pintype "passive"))
      (node (ref "C11") (pin "1") (pinfunction "P$1_1") (pintype "passive"))
      (node (ref "C12") (pin "1") (pinfunction "P$1_1") (pintype "passive"))
      (node (ref "C13") (pin "1") (pinfunction "P$1_1") (pintype "passive"))
      (node (ref "C14") (pin "2") (pinfunction "P$2_2") (pintype "passive"))
      (node (ref "C15") (pin "2") (pinfunction "P$2_2") (pintype "passive"))
      (node (ref "C16") (pin "2") (pinfunction "P$2_2") (pintype "passive"))
      (node (ref "C17") (pin "2") (pinfunction "P$2_2") (pintype "passive"))
      (node (ref "C18") (pin "2") (pinfunction "P$2_2") (pintype "passive"))
      (node (ref "C19") (pin "1") (pinfunction "P$1_1") (pintype "passive"))
      (node (ref "C2") (pin "2") (pinfunction "P$2_2") (pintype "passive"))
      (node (ref "C20") (pin "1") (pinfunction "P$1_1") (pintype "passive"))
      (node (ref "C21") (pin "1") (pinfunction "P$1_1") (pintype "passive"))
      (node (ref "C22") (pin "1") (pinfunction "P$1_1") (pintype "passive"))
      (node (ref "C23") (pin "1") (pinfunction "P$1_1") (pintype "passive"))
      (node (ref "C24") (pin "2") (pinfunction "P$2_2") (pintype "passive"))
      (node (ref "C25") (pin "-") (pinfunction "-_-") (pintype "passive"))
      (node (ref "C26") (pin "-") (pinfunction "-_-") (pintype "passive"))
      (node (ref "C3") (pin "2") (pinfunction "P$2_2") (pintype "passive"))
      (node (ref "C4") (pin "1") (pinfunction "P$1_1") (pintype "passive"))
      (node (ref "C8") (pin "1") (pinfunction "P$1_1") (pintype "passive"))
      (node (ref "C9") (pin "1") (pinfunction "P$1_1") (pintype "passive"))
      (node (ref "D3") (pin "A") (pinfunction "A_A") (pintype "passive"))
      (node (ref "IC1") (pin "3") (pinfunction "GND_3") (pintype "power_in"))
      (node (ref "IC1") (pin "5") (pinfunction "EN_5") (pintype "input"))
      (node (ref "IC1") (pin "6") (pinfunction "GND_6") (pintype "power_in"))
      (node (ref "IC2") (pin "5") (pinfunction "I_5") (pintype "input"))
      (node (ref "IC2") (pin "7") (pinfunction "GND_7") (pintype "power_in"))
      (node (ref "IC3") (pin "7") (pinfunction "GND_7") (pintype "power_in"))
      (node (ref "R1") (pin "2") (pinfunction "2_2") (pintype "passive"))
      (node (ref "R15") (pin "2") (pinfunction "2_2") (pintype "passive"))
      (node (ref "R3") (pin "1") (pinfunction "1_1") (pintype "passive"))
      (node (ref "R4") (pin "2") (pinfunction "2_2") (pintype "passive"))
      (node (ref "R5") (pin "2") (pinfunction "2_2") (pintype "passive"))
      (node (ref "R6") (pin "2") (pinfunction "2_2") (pintype "passive"))
      (node (ref "R9") (pin "1") (pinfunction "1_1") (pintype "passive"))
      (node (ref "S1") (pin "1") (pinfunction "S_1") (pintype "passive"))
      (node (ref "S1") (pin "2") (pinfunction "S1_2") (pintype "passive"))
      (node (ref "S2") (pin "1") (pinfunction "S_1") (pintype "passive"))
      (node (ref "S2") (pin "2") (pinfunction "S1_2") (pintype "passive"))
      (node (ref "S3") (pin "1") (pinfunction "S_1") (pintype "passive"))
      (node (ref "S3") (pin "2") (pinfunction "S1_2") (pintype "passive"))
      (node (ref "S4") (pin "1") (pinfunction "S_1") (pintype "passive"))
      (node (ref "S4") (pin "2") (pinfunction "S1_2") (pintype "passive"))
      (node (ref "S5") (pin "1") (pinfunction "S_1") (pintype "passive"))
      (node (ref "S5") (pin "2") (pinfunction "S1_2") (pintype "passive"))
      (node (ref "S6") (pin "1") (pinfunction "S_1") (pintype "passive"))
      (node (ref "S6") (pin "2") (pinfunction "S1_2") (pintype "passive"))
      (node (ref "U$1") (pin "P$19") (pinfunction "GND1_P$19") (pintype "bidirectional"))
      (node (ref "U$1") (pin "P$20") (pinfunction "GND2_P$20") (pintype "bidirectional"))
      (node (ref "U$1") (pin "P$41") (pinfunction "GND3_P$41") (pintype "bidirectional"))
      (node (ref "U$1") (pin "P$42") (pinfunction "GND4_P$42") (pintype "bidirectional"))
      (node (ref "U$1") (pin "P$62") (pinfunction "GND5_P$62") (pintype "bidirectional"))
      (node (ref "U$1") (pin "P$69") (pinfunction "GND6_P$69") (pintype "bidirectional"))
      (node (ref "U$1") (pin "P$70") (pinfunction "GND7_P$70") (pintype "bidirectional"))
      (node (ref "U$1") (pin "P$78") (pinfunction "GND8_P$78") (pintype "bidirectional"))
      (node (ref "U$10") (pin "P$24") (pinfunction "VSS2_P$24") (pintype "bidirectional"))
      (node (ref "U$10") (pin "P$25") (pinfunction "VSS_P$25") (pintype "bidirectional"))
      (node (ref "U$10") (pin "P$26") (pinfunction "BM0_P$26") (pintype "bidirectional"))
      (node (ref "U$30") (pin "10") (pinfunction "GND_10") (pintype "bidirectional"))
      (node (ref "U$30") (pin "19") (pinfunction "GND_19") (pintype "bidirectional"))
      (node (ref "U$30") (pin "2") (pinfunction "A0_2") (pintype "bidirectional"))
      (node (ref "U$30") (pin "24") (pinfunction "GND_24") (pintype "bidirectional"))
      (node (ref "U$30") (pin "3") (pinfunction "A1_3") (pintype "bidirectional"))
      (node (ref "U$30") (pin "4") (pinfunction "A2_4") (pintype "bidirectional"))
      (node (ref "U$30") (pin "5") (pinfunction "A3_5") (pintype "bidirectional"))
      (node (ref "U$33") (pin "10") (pinfunction "GND_10") (pintype "bidirectional"))
      (node (ref "U$33") (pin "19") (pinfunction "GND_19") (pintype "bidirectional"))
      (node (ref "U$33") (pin "24") (pinfunction "GND_24") (pintype "bidirectional"))
      (node (ref "U$33") (pin "3") (pinfunction "A1_3") (pintype "bidirectional"))
      (node (ref "U$33") (pin "4") (pinfunction "A2_4") (pintype "bidirectional"))
      (node (ref "U$33") (pin "5") (pinfunction "A3_5") (pintype "bidirectional"))
      (node (ref "U$36") (pin "10") (pinfunction "GND_10") (pintype "bidirectional"))
      (node (ref "U$36") (pin "19") (pinfunction "GND_19") (pintype "bidirectional"))
      (node (ref "U$36") (pin "2") (pinfunction "A0_2") (pintype "bidirectional"))
      (node (ref "U$36") (pin "24") (pinfunction "GND_24") (pintype "bidirectional"))
      (node (ref "U$36") (pin "4") (pinfunction "A2_4") (pintype "bidirectional"))
      (node (ref "U$36") (pin "5") (pinfunction "A3_5") (pintype "bidirectional"))
      (node (ref "U$42") (pin "PIN1") (pinfunction "PIN1_PIN1") (pintype "bidirectional"))
      (node (ref "U$51") (pin "10") (pinfunction "GND_10") (pintype "bidirectional"))
      (node (ref "U$51") (pin "19") (pinfunction "GND_19") (pintype "bidirectional"))
      (node (ref "U$51") (pin "24") (pinfunction "GND_24") (pintype "bidirectional"))
      (node (ref "U$51") (pin "4") (pinfunction "A2_4") (pintype "bidirectional"))
      (node (ref "U$51") (pin "5") (pinfunction "A3_5") (pintype "bidirectional"))
      (node (ref "U1") (pin "2") (pinfunction "GND_2") (pintype "bidirectional"))
      (node (ref "X1") (pin "2") (pinfunction "KL_2") (pintype "passive"))
    )
    (net (code "16") (name "LCD_CLOCK") (class "Default")
      (node (ref "U$1") (pin "P$3") (pinfunction "PA5_P$3") (pintype "bidirectional"))
      (node (ref "U$10") (pin "P$32") (pinfunction "D0/SCK_P$32") (pintype "bidirectional"))
    )
    (net (code "17") (name "LCD_CS") (class "Default")
      (node (ref "U$1") (pin "P$7") (pinfunction "PC5_P$7") (pintype "bidirectional"))
      (node (ref "U$10") (pin "P$28") (pinfunction "CS0/A2_P$28") (pintype "bidirectional"))
    )
    (net (code "18") (name "LCD_DATA") (class "Default")
      (node (ref "U$1") (pin "P$5") (pinfunction "PA7_P$5") (pintype "bidirectional"))
      (node (ref "U$10") (pin "P$31") (pinfunction "D3/SDA_P$31") (pintype "bidirectional"))
    )
    (net (code "19") (name "LCD_RESET") (class "Default")
      (node (ref "U$1") (pin "P$8") (pinfunction "PB0_P$8") (pintype "bidirectional"))
      (node (ref "U$10") (pin "P$29") (pinfunction "RST_P$29") (pintype "bidirectional"))
    )
    (net (code "20") (name "Net-(C1-P$1)") (class "Default")
      (node (ref "C1") (pin "1") (pinfunction "P$1_1") (pintype "passive"))
      (node (ref "D1") (pin "C") (pinfunction "C_C") (pintype "passive"))
      (node (ref "U$10") (pin "P$1") (pinfunction "A1+_P$1") (pintype "bidirectional"))
    )
    (net (code "21") (name "Net-(C6-P$1)") (class "Default")
      (node (ref "C6") (pin "1") (pinfunction "P$1_1") (pintype "passive"))
      (node (ref "U$10") (pin "P$20") (pinfunction "VB1-_P$20") (pintype "bidirectional"))
    )
    (net (code "22") (name "Net-(C6-P$2)") (class "Default")
      (node (ref "C6") (pin "2") (pinfunction "P$2_2") (pintype "passive"))
      (node (ref "U$10") (pin "P$19") (pinfunction "VB1+_P$19") (pintype "bidirectional"))
    )
    (net (code "23") (name "Net-(C7-P$1)") (class "Default")
      (node (ref "C7") (pin "1") (pinfunction "P$1_1") (pintype "passive"))
      (node (ref "U$10") (pin "P$21") (pinfunction "VB0-_P$21") (pintype "bidirectional"))
    )
    (net (code "24") (name "Net-(C7-P$2)") (class "Default")
      (node (ref "C7") (pin "2") (pinfunction "P$2_2") (pintype "passive"))
      (node (ref "U$10") (pin "P$18") (pinfunction "VB0+_P$18") (pintype "bidirectional"))
    )
    (net (code "25") (name "Net-(C8-P$2)") (class "Default")
      (node (ref "C8") (pin "2") (pinfunction "P$2_2") (pintype "passive"))
      (node (ref "R9") (pin "2") (pinfunction "2_2") (pintype "passive"))
      (node (ref "U$10") (pin "P$17") (pinfunction "VLCD_P$17") (pintype "bidirectional"))
    )
    (net (code "26") (name "Net-(IC1-FB)") (class "Default")
      (node (ref "IC1") (pin "4") (pinfunction "FB_4") (pintype "input"))
      (node (ref "R2") (pin "1") (pinfunction "1_1") (pintype "passive"))
      (node (ref "R3") (pin "2") (pinfunction "2_2") (pintype "passive"))
    )
    (net (code "27") (name "Net-(IC1-IN)") (class "Default")
      (node (ref "C25") (pin "+") (pinfunction "+_+") (pintype "passive"))
      (node (ref "IC1") (pin "1") (pinfunction "IN_1") (pintype "input"))
      (node (ref "PTC1") (pin "P$1") (pinfunction "1_P$1") (pintype "passive"))
    )
    (net (code "28") (name "Net-(IC1-OUT)") (class "Default")
      (node (ref "D3") (pin "C") (pinfunction "C_C") (pintype "passive"))
      (node (ref "IC1") (pin "2") (pinfunction "OUT_2") (pintype "output"))
      (node (ref "L2") (pin "1") (pinfunction "1_1") (pintype "passive"))
    )
    (net (code "29") (name "Net-(LED1-BGND)") (class "Default")
      (node (ref "LED1") (pin "1") (pinfunction "BGND_1") (pintype "power_in"))
      (node (ref "U$30") (pin "8") (pinfunction "/OUT2_8") (pintype "bidirectional"))
    )
    (net (code "30") (name "Net-(LED1-GGND)") (class "Default")
      (node (ref "LED1") (pin "2") (pinfunction "GGND_2") (pintype "power_in"))
      (node (ref "U$30") (pin "7") (pinfunction "/OUT1_7") (pintype "bidirectional"))
    )
    (net (code "31") (name "Net-(LED1-RGND)") (class "Default")
      (node (ref "LED1") (pin "3") (pinfunction "RGND_3") (pintype "power_in"))
      (node (ref "U$30") (pin "6") (pinfunction "/OUT0_6") (pintype "bidirectional"))
    )
    (net (code "32") (name "Net-(LED2-BGND)") (class "Default")
      (node (ref "LED2") (pin "1") (pinfunction "BGND_1") (pintype "power_in"))
      (node (ref "U$30") (pin "12") (pinfunction "/OUT5_12") (pintype "bidirectional"))
    )
    (net (code "33") (name "Net-(LED2-GGND)") (class "Default")
      (node (ref "LED2") (pin "2") (pinfunction "GGND_2") (pintype "power_in"))
      (node (ref "U$30") (pin "11") (pinfunction "/OUT4_11") (pintype "bidirectional"))
    )
    (net (code "34") (name "Net-(LED2-RGND)") (class "Default")
      (node (ref "LED2") (pin "3") (pinfunction "RGND_3") (pintype "power_in"))
      (node (ref "U$30") (pin "9") (pinfunction "/OUT3_9") (pintype "bidirectional"))
    )
    (net (code "35") (name "Net-(LED3-BGND)") (class "Default")
      (node (ref "LED3") (pin "1") (pinfunction "BGND_1") (pintype "power_in"))
      (node (ref "U$30") (pin "15") (pinfunction "/OUT8_15") (pintype "bidirectional"))
    )
    (net (code "36") (name "Net-(LED3-GGND)") (class "Default")
      (node (ref "LED3") (pin "2") (pinfunction "GGND_2") (pintype "power_in"))
      (node (ref "U$30") (pin "14") (pinfunction "/OUT7_14") (pintype "bidirectional"))
    )
    (net (code "37") (name "Net-(LED3-RGND)") (class "Default")
      (node (ref "LED3") (pin "3") (pinfunction "RGND_3") (pintype "power_in"))
      (node (ref "U$30") (pin "13") (pinfunction "/OUT6_13") (pintype "bidirectional"))
    )
    (net (code "38") (name "Net-(LED4-BGND)") (class "Default")
      (node (ref "LED4") (pin "1") (pinfunction "BGND_1") (pintype "power_in"))
      (node (ref "U$30") (pin "18") (pinfunction "/OUT11_18") (pintype "bidirectional"))
    )
    (net (code "39") (name "Net-(LED4-GGND)") (class "Default")
      (node (ref "LED4") (pin "2") (pinfunction "GGND_2") (pintype "power_in"))
      (node (ref "U$30") (pin "17") (pinfunction "/OUT10_17") (pintype "bidirectional"))
    )
    (net (code "40") (name "Net-(LED4-RGND)") (class "Default")
      (node (ref "LED4") (pin "3") (pinfunction "RGND_3") (pintype "power_in"))
      (node (ref "U$30") (pin "16") (pinfunction "/OUT9_16") (pintype "bidirectional"))
    )
    (net (code "41") (name "Net-(LED5-BGND)") (class "Default")
      (node (ref "LED5") (pin "1") (pinfunction "BGND_1") (pintype "power_in"))
      (node (ref "U$30") (pin "22") (pinfunction "/OUT14_22") (pintype "bidirectional"))
    )
    (net (code "42") (name "Net-(LED5-GGND)") (class "Default")
      (node (ref "LED5") (pin "2") (pinfunction "GGND_2") (pintype "power_in"))
      (node (ref "U$30") (pin "21") (pinfunction "/OUT13_21") (pintype "bidirectional"))
    )
    (net (code "43") (name "Net-(LED5-RGND)") (class "Default")
      (node (ref "LED5") (pin "3") (pinfunction "RGND_3") (pintype "power_in"))
      (node (ref "U$30") (pin "20") (pinfunction "/OUT12_20") (pintype "bidirectional"))
    )
    (net (code "44") (name "Net-(LED6-BGND)") (class "Default")
      (node (ref "LED6") (pin "1") (pinfunction "BGND_1") (pintype "power_in"))
      (node (ref "U$33") (pin "8") (pinfunction "/OUT2_8") (pintype "bidirectional"))
    )
    (net (code "45") (name "Net-(LED6-GGND)") (class "Default")
      (node (ref "LED6") (pin "2") (pinfunction "GGND_2") (pintype "power_in"))
      (node (ref "U$33") (pin "7") (pinfunction "/OUT1_7") (pintype "bidirectional"))
    )
    (net (code "46") (name "Net-(LED6-RGND)") (class "Default")
      (node (ref "LED6") (pin "3") (pinfunction "RGND_3") (pintype "power_in"))
      (node (ref "U$33") (pin "6") (pinfunction "/OUT0_6") (pintype "bidirectional"))
    )
    (net (code "47") (name "Net-(LED7-BGND)") (class "Default")
      (node (ref "LED7") (pin "1") (pinfunction "BGND_1") (pintype "power_in"))
      (node (ref "U$33") (pin "12") (pinfunction "/OUT5_12") (pintype "bidirectional"))
    )
    (net (code "48") (name "Net-(LED7-GGND)") (class "Default")
      (node (ref "LED7") (pin "2") (pinfunction "GGND_2") (pintype "power_in"))
      (node (ref "U$33") (pin "11") (pinfunction "/OUT4_11") (pintype "bidirectional"))
    )
    (net (code "49") (name "Net-(LED7-RGND)") (class "Default")
      (node (ref "LED7") (pin "3") (pinfunction "RGND_3") (pintype "power_in"))
      (node (ref "U$33") (pin "9") (pinfunction "/OUT3_9") (pintype "bidirectional"))
    )
    (net (code "50") (name "Net-(LED8-BGND)") (class "Default")
      (node (ref "LED8") (pin "1") (pinfunction "BGND_1") (pintype "power_in"))
      (node (ref "U$33") (pin "15") (pinfunction "/OUT8_15") (pintype "bidirectional"))
    )
    (net (code "51") (name "Net-(LED8-GGND)") (class "Default")
      (node (ref "LED8") (pin "2") (pinfunction "GGND_2") (pintype "power_in"))
      (node (ref "U$33") (pin "14") (pinfunction "/OUT7_14") (pintype "bidirectional"))
    )
    (net (code "52") (name "Net-(LED8-RGND)") (class "Default")
      (node (ref "LED8") (pin "3") (pinfunction "RGND_3") (pintype "power_in"))
      (node (ref "U$33") (pin "13") (pinfunction "/OUT6_13") (pintype "bidirectional"))
    )
    (net (code "53") (name "Net-(LED9-BGND)") (class "Default")
      (node (ref "LED9") (pin "1") (pinfunction "BGND_1") (pintype "power_in"))
      (node (ref "U$33") (pin "18") (pinfunction "/OUT11_18") (pintype "bidirectional"))
    )
    (net (code "54") (name "Net-(LED9-GGND)") (class "Default")
      (node (ref "LED9") (pin "2") (pinfunction "GGND_2") (pintype "power_in"))
      (node (ref "U$33") (pin "17") (pinfunction "/OUT10_17") (pintype "bidirectional"))
    )
    (net (code "55") (name "Net-(LED9-RGND)") (class "Default")
      (node (ref "LED9") (pin "3") (pinfunction "RGND_3") (pintype "power_in"))
      (node (ref "U$33") (pin "16") (pinfunction "/OUT9_16") (pintype "bidirectional"))
    )
    (net (code "56") (name "Net-(LED10-BGND)") (class "Default")
      (node (ref "LED10") (pin "1") (pinfunction "BGND_1") (pintype "power_in"))
      (node (ref "U$33") (pin "22") (pinfunction "/OUT14_22") (pintype "bidirectional"))
    )
    (net (code "57") (name "Net-(LED10-GGND)") (class "Default")
      (node (ref "LED10") (pin "2") (pinfunction "GGND_2") (pintype "power_in"))
      (node (ref "U$33") (pin "21") (pinfunction "/OUT13_21") (pintype "bidirectional"))
    )
    (net (code "58") (name "Net-(LED10-RGND)") (class "Default")
      (node (ref "LED10") (pin "3") (pinfunction "RGND_3") (pintype "power_in"))
      (node (ref "U$33") (pin "20") (pinfunction "/OUT12_20") (pintype "bidirectional"))
    )
    (net (code "59") (name "Net-(LED11-BGND)") (class "Default")
      (node (ref "LED11") (pin "1") (pinfunction "BGND_1") (pintype "power_in"))
      (node (ref "U$36") (pin "8") (pinfunction "/OUT2_8") (pintype "bidirectional"))
    )
    (net (code "60") (name "Net-(LED11-GGND)") (class "Default")
      (node (ref "LED11") (pin "2") (pinfunction "GGND_2") (pintype "power_in"))
      (node (ref "U$36") (pin "7") (pinfunction "/OUT1_7") (pintype "bidirectional"))
    )
    (net (code "61") (name "Net-(LED11-RGND)") (class "Default")
      (node (ref "LED11") (pin "3") (pinfunction "RGND_3") (pintype "power_in"))
      (node (ref "U$36") (pin "6") (pinfunction "/OUT0_6") (pintype "bidirectional"))
    )
    (net (code "62") (name "Net-(LED12-BGND)") (class "Default")
      (node (ref "LED12") (pin "1") (pinfunction "BGND_1") (pintype "power_in"))
      (node (ref "U$36") (pin "12") (pinfunction "/OUT5_12") (pintype "bidirectional"))
    )
    (net (code "63") (name "Net-(LED12-GGND)") (class "Default")
      (node (ref "LED12") (pin "2") (pinfunction "GGND_2") (pintype "power_in"))
      (node (ref "U$36") (pin "11") (pinfunction "/OUT4_11") (pintype "bidirectional"))
    )
    (net (code "64") (name "Net-(LED12-RGND)") (class "Default")
      (node (ref "LED12") (pin "3") (pinfunction "RGND_3") (pintype "power_in"))
      (node (ref "U$36") (pin "9") (pinfunction "/OUT3_9") (pintype "bidirectional"))
    )
    (net (code "65") (name "Net-(LED13-BGND)") (class "Default")
      (node (ref "LED13") (pin "1") (pinfunction "BGND_1") (pintype "power_in"))
      (node (ref "U$36") (pin "15") (pinfunction "/OUT8_15") (pintype "bidirectional"))
    )
    (net (code "66") (name "Net-(LED13-GGND)") (class "Default")
      (node (ref "LED13") (pin "2") (pinfunction "GGND_2") (pintype "power_in"))
      (node (ref "U$36") (pin "14") (pinfunction "/OUT7_14") (pintype "bidirectional"))
    )
    (net (code "67") (name "Net-(LED13-RGND)") (class "Default")
      (node (ref "LED13") (pin "3") (pinfunction "RGND_3") (pintype "power_in"))
      (node (ref "U$36") (pin "13") (pinfunction "/OUT6_13") (pintype "bidirectional"))
    )
    (net (code "68") (name "Net-(LED14-BGND)") (class "Default")
      (node (ref "LED14") (pin "1") (pinfunction "BGND_1") (pintype "power_in"))
      (node (ref "U$36") (pin "18") (pinfunction "/OUT11_18") (pintype "bidirectional"))
    )
    (net (code "69") (name "Net-(LED14-GGND)") (class "Default")
      (node (ref "LED14") (pin "2") (pinfunction "GGND_2") (pintype "power_in"))
      (node (ref "U$36") (pin "17") (pinfunction "/OUT10_17") (pintype "bidirectional"))
    )
    (net (code "70") (name "Net-(LED14-RGND)") (class "Default")
      (node (ref "LED14") (pin "3") (pinfunction "RGND_3") (pintype "power_in"))
      (node (ref "U$36") (pin "16") (pinfunction "/OUT9_16") (pintype "bidirectional"))
    )
    (net (code "71") (name "Net-(LED15-BGND)") (class "Default")
      (node (ref "LED15") (pin "1") (pinfunction "BGND_1") (pintype "power_in"))
      (node (ref "U$36") (pin "22") (pinfunction "/OUT14_22") (pintype "bidirectional"))
    )
    (net (code "72") (name "Net-(LED15-GGND)") (class "Default")
      (node (ref "LED15") (pin "2") (pinfunction "GGND_2") (pintype "power_in"))
      (node (ref "U$36") (pin "21") (pinfunction "/OUT13_21") (pintype "bidirectional"))
    )
    (net (code "73") (name "Net-(LED15-RGND)") (class "Default")
      (node (ref "LED15") (pin "3") (pinfunction "RGND_3") (pintype "power_in"))
      (node (ref "U$36") (pin "20") (pinfunction "/OUT12_20") (pintype "bidirectional"))
    )
    (net (code "74") (name "Net-(LED16-BGND)") (class "Default")
      (node (ref "LED16") (pin "1") (pinfunction "BGND_1") (pintype "power_in"))
      (node (ref "U$51") (pin "8") (pinfunction "/OUT2_8") (pintype "bidirectional"))
    )
    (net (code "75") (name "Net-(LED16-GGND)") (class "Default")
      (node (ref "LED16") (pin "2") (pinfunction "GGND_2") (pintype "power_in"))
      (node (ref "U$51") (pin "7") (pinfunction "/OUT1_7") (pintype "bidirectional"))
    )
    (net (code "76") (name "Net-(LED16-RGND)") (class "Default")
      (node (ref "LED16") (pin "3") (pinfunction "RGND_3") (pintype "power_in"))
      (node (ref "U$51") (pin "6") (pinfunction "/OUT0_6") (pintype "bidirectional"))
    )
    (net (code "77") (name "Net-(LED17-BGND)") (class "Default")
      (node (ref "LED17") (pin "1") (pinfunction "BGND_1") (pintype "power_in"))
      (node (ref "U$51") (pin "12") (pinfunction "/OUT5_12") (pintype "bidirectional"))
    )
    (net (code "78") (name "Net-(LED17-GGND)") (class "Default")
      (node (ref "LED17") (pin "2") (pinfunction "GGND_2") (pintype "power_in"))
      (node (ref "U$51") (pin "11") (pinfunction "/OUT4_11") (pintype "bidirectional"))
    )
    (net (code "79") (name "Net-(LED17-RGND)") (class "Default")
      (node (ref "LED17") (pin "3") (pinfunction "RGND_3") (pintype "power_in"))
      (node (ref "U$51") (pin "9") (pinfunction "/OUT3_9") (pintype "bidirectional"))
    )
    (net (code "80") (name "Net-(LED18-BGND)") (class "Default")
      (node (ref "LED18") (pin "1") (pinfunction "BGND_1") (pintype "power_in"))
      (node (ref "U$51") (pin "15") (pinfunction "/OUT8_15") (pintype "bidirectional"))
    )
    (net (code "81") (name "Net-(LED18-GGND)") (class "Default")
      (node (ref "LED18") (pin "2") (pinfunction "GGND_2") (pintype "power_in"))
      (node (ref "U$51") (pin "14") (pinfunction "/OUT7_14") (pintype "bidirectional"))
    )
    (net (code "82") (name "Net-(LED18-RGND)") (class "Default")
      (node (ref "LED18") (pin "3") (pinfunction "RGND_3") (pintype "power_in"))
      (node (ref "U$51") (pin "13") (pinfunction "/OUT6_13") (pintype "bidirectional"))
    )
    (net (code "83") (name "Net-(LED19-BGND)") (class "Default")
      (node (ref "LED19") (pin "1") (pinfunction "BGND_1") (pintype "power_in"))
      (node (ref "U$51") (pin "18") (pinfunction "/OUT11_18") (pintype "bidirectional"))
    )
    (net (code "84") (name "Net-(LED19-GGND)") (class "Default")
      (node (ref "LED19") (pin "2") (pinfunction "GGND_2") (pintype "power_in"))
      (node (ref "U$51") (pin "17") (pinfunction "/OUT10_17") (pintype "bidirectional"))
    )
    (net (code "85") (name "Net-(LED19-RGND)") (class "Default")
      (node (ref "LED19") (pin "3") (pinfunction "RGND_3") (pintype "power_in"))
      (node (ref "U$51") (pin "16") (pinfunction "/OUT9_16") (pintype "bidirectional"))
    )
    (net (code "86") (name "Net-(LED20-BGND)") (class "Default")
      (node (ref "LED20") (pin "1") (pinfunction "BGND_1") (pintype "power_in"))
      (node (ref "U$51") (pin "22") (pinfunction "/OUT14_22") (pintype "bidirectional"))
    )
    (net (code "87") (name "Net-(LED20-GGND)") (class "Default")
      (node (ref "LED20") (pin "2") (pinfunction "GGND_2") (pintype "power_in"))
      (node (ref "U$51") (pin "21") (pinfunction "/OUT13_21") (pintype "bidirectional"))
    )
    (net (code "88") (name "Net-(LED20-RGND)") (class "Default")
      (node (ref "LED20") (pin "3") (pinfunction "RGND_3") (pintype "power_in"))
      (node (ref "U$51") (pin "20") (pinfunction "/OUT12_20") (pintype "bidirectional"))
    )
    (net (code "89") (name "Net-(U$10-A2+)") (class "Default")
      (node (ref "U$10") (pin "P$14") (pinfunction "C1-_P$14") (pintype "bidirectional"))
      (node (ref "U$10") (pin "P$2") (pinfunction "A2+_P$2") (pintype "bidirectional"))
    )
    (net (code "90") (name "Net-(U$10-A3+)") (class "Default")
      (node (ref "U$10") (pin "P$15") (pinfunction "C2-_P$15") (pintype "bidirectional"))
      (node (ref "U$10") (pin "P$3") (pinfunction "A3+_P$3") (pintype "bidirectional"))
    )
    (net (code "91") (name "Net-(U$10-C3-)") (class "Default")
      (node (ref "R1") (pin "1") (pinfunction "1_1") (pintype "passive"))
      (node (ref "U$10") (pin "P$16") (pinfunction "C3-_P$16") (pintype "bidirectional"))
      (node (ref "U1") (pin "3") (pinfunction "FB_3") (pintype "bidirectional"))
    )
    (net (code "92") (name "Net-(U$30-REXT)") (class "Default")
      (node (ref "R4") (pin "1") (pinfunction "1_1") (pintype "passive"))
      (node (ref "U$30") (pin "1") (pinfunction "REXT_1") (pintype "bidirectional"))
    )
    (net (code "93") (name "Net-(U$33-REXT)") (class "Default")
      (node (ref "R5") (pin "1") (pinfunction "1_1") (pintype "passive"))
      (node (ref "U$33") (pin "1") (pinfunction "REXT_1") (pintype "bidirectional"))
    )
    (net (code "94") (name "Net-(U$36-REXT)") (class "Default")
      (node (ref "R6") (pin "1") (pinfunction "1_1") (pintype "passive"))
      (node (ref "U$36") (pin "1") (pinfunction "REXT_1") (pintype "bidirectional"))
    )
    (net (code "95") (name "Net-(U$51-REXT)") (class "Default")
      (node (ref "R15") (pin "1") (pinfunction "1_1") (pintype "passive"))
      (node (ref "U$51") (pin "1") (pinfunction "REXT_1") (pintype "bidirectional"))
    )
    (net (code "96") (name "Net-(U1-SW)") (class "Default")
      (node (ref "D1") (pin "A") (pinfunction "A_A") (pintype "passive"))
      (node (ref "L1") (pin "1") (pinfunction "1_1") (pintype "passive"))
      (node (ref "U1") (pin "1") (pinfunction "SW_1") (pintype "bidirectional"))
    )
    (net (code "97") (name "SCL") (class "Default")
      (node (ref "R8") (pin "1") (pinfunction "1_1") (pintype "passive"))
      (node (ref "U$1") (pin "P$21") (pinfunction "PB10_P$21") (pintype "bidirectional"))
      (node (ref "U$30") (pin "26") (pinfunction "SCL_26") (pintype "bidirectional"))
      (node (ref "U$33") (pin "26") (pinfunction "SCL_26") (pintype "bidirectional"))
      (node (ref "U$36") (pin "26") (pinfunction "SCL_26") (pintype "bidirectional"))
      (node (ref "U$51") (pin "26") (pinfunction "SCL_26") (pintype "bidirectional"))
    )
    (net (code "98") (name "SDA") (class "Default")
      (node (ref "R7") (pin "1") (pinfunction "1_1") (pintype "passive"))
      (node (ref "U$1") (pin "P$22") (pinfunction "PB11_P$22") (pintype "bidirectional"))
      (node (ref "U$30") (pin "27") (pinfunction "SDA_27") (pintype "bidirectional"))
      (node (ref "U$33") (pin "27") (pinfunction "SDA_27") (pintype "bidirectional"))
      (node (ref "U$36") (pin "27") (pinfunction "SDA_27") (pintype "bidirectional"))
      (node (ref "U$51") (pin "27") (pinfunction "SDA_27") (pintype "bidirectional"))
    )
    (net (code "99") (name "SW1") (class "Default")
      (node (ref "C22") (pin "2") (pinfunction "P$2_2") (pintype "passive"))
      (node (ref "IC3") (pin "1") (pinfunction "I_1") (pintype "input"))
      (node (ref "R16") (pin "1") (pinfunction "1_1") (pintype "passive"))
      (node (ref "S1") (pin "3") (pinfunction "P_3") (pintype "passive"))
      (node (ref "S1") (pin "4") (pinfunction "P1_4") (pintype "passive"))
    )
    (net (code "100") (name "SW1S") (class "Default")
      (node (ref "IC3") (pin "2") (pinfunction "O_2") (pintype "output"))
      (node (ref "U$1") (pin "P$11") (pinfunction "PE8_P$11") (pintype "bidirectional"))
    )
    (net (code "101") (name "SW2") (class "Default")
      (node (ref "C23") (pin "2") (pinfunction "P$2_2") (pintype "passive"))
      (node (ref "IC3") (pin "3") (pinfunction "I_3") (pintype "input"))
      (node (ref "R17") (pin "1") (pinfunction "1_1") (pintype "passive"))
      (node (ref "S2") (pin "3") (pinfunction "P_3") (pintype "passive"))
      (node (ref "S2") (pin "4") (pinfunction "P1_4") (pintype "passive"))
    )
    (net (code "102") (name "SW2S") (class "Default")
      (node (ref "IC3") (pin "4") (pinfunction "O_4") (pintype "output"))
      (node (ref "U$1") (pin "P$9") (pinfunction "PB1_P$9") (pintype "bidirectional"))
    )
    (net (code "103") (name "SW3") (class "Default")
      (node (ref "C20") (pin "2") (pinfunction "P$2_2") (pintype "passive"))
      (node (ref "IC3") (pin "11") (pinfunction "I_11") (pintype "input"))
      (node (ref "R18") (pin "1") (pinfunction "1_1") (pintype "passive"))
      (node (ref "S3") (pin "3") (pinfunction "P_3") (pintype "passive"))
      (node (ref "S3") (pin "4") (pinfunction "P1_4") (pintype "passive"))
    )
    (net (code "104") (name "SW3S") (class "Default")
      (node (ref "IC3") (pin "10") (pinfunction "O_10") (pintype "output"))
      (node (ref "U$1") (pin "P$15") (pinfunction "PE12_P$15") (pintype "bidirectional"))
    )
    (net (code "105") (name "SW4") (class "Default")
      (node (ref "C19") (pin "2") (pinfunction "P$2_2") (pintype "passive"))
      (node (ref "IC3") (pin "13") (pinfunction "I_13") (pintype "input"))
      (node (ref "R19") (pin "1") (pinfunction "1_1") (pintype "passive"))
      (node (ref "S4") (pin "3") (pinfunction "P_3") (pintype "passive"))
      (node (ref "S4") (pin "4") (pinfunction "P1_4") (pintype "passive"))
    )
    (net (code "106") (name "SW4S") (class "Default")
      (node (ref "IC3") (pin "12") (pinfunction "O_12") (pintype "output"))
      (node (ref "U$1") (pin "P$13") (pinfunction "PE10_P$13") (pintype "bidirectional"))
    )
    (net (code "107") (name "SW5") (class "Default")
      (node (ref "C21") (pin "2") (pinfunction "P$2_2") (pintype "passive"))
      (node (ref "IC3") (pin "9") (pinfunction "I_9") (pintype "input"))
      (node (ref "R20") (pin "1") (pinfunction "1_1") (pintype "passive"))
      (node (ref "S5") (pin "3") (pinfunction "P_3") (pintype "passive"))
      (node (ref "S5") (pin "4") (pinfunction "P1_4") (pintype "passive"))
    )
    (net (code "108") (name "SW5S") (class "Default")
      (node (ref "IC3") (pin "8") (pinfunction "O_8") (pintype "output"))
      (node (ref "U$1") (pin "P$17") (pinfunction "PE14_P$17") (pintype "bidirectional"))
    )
    (net (code "109") (name "SW6") (class "Default")
      (node (ref "C4") (pin "2") (pinfunction "P$2_2") (pintype "passive"))
      (node (ref "IC3") (pin "5") (pinfunction "I_5") (pintype "input"))
      (node (ref "R21") (pin "1") (pinfunction "1_1") (pintype "passive"))
      (node (ref "S6") (pin "3") (pinfunction "P_3") (pintype "passive"))
      (node (ref "S6") (pin "4") (pinfunction "P1_4") (pintype "passive"))
    )
    (net (code "110") (name "SW6S") (class "Default")
      (node (ref "IC3") (pin "6") (pinfunction "O_6") (pintype "output"))
      (node (ref "U$1") (pin "P$10") (pinfunction "PE7_P$10") (pintype "bidirectional"))
    )
    (net (code "111") (name "unconnected-(IC2F-O-Pad6)") (class "Default")
      (node (ref "IC2") (pin "6") (pinfunction "O_6") (pintype "output"))
    )
    (net (code "112") (name "unconnected-(U$1A-PA4-PadP$2)") (class "Default")
      (node (ref "U$1") (pin "P$2") (pinfunction "PA4_P$2") (pintype "bidirectional"))
    )
    (net (code "113") (name "unconnected-(U$1A-PA6-PadP$4)") (class "Default")
      (node (ref "U$1") (pin "P$4") (pinfunction "PA6_P$4") (pintype "bidirectional"))
    )
    (net (code "114") (name "unconnected-(U$1A-PE9-PadP$12)") (class "Default")
      (node (ref "U$1") (pin "P$12") (pinfunction "PE9_P$12") (pintype "bidirectional"))
    )
    (net (code "115") (name "unconnected-(U$1A-PE11-PadP$14)") (class "Default")
      (node (ref "U$1") (pin "P$14") (pinfunction "PE11_P$14") (pintype "bidirectional"))
    )
    (net (code "116") (name "unconnected-(U$1A-PE13-PadP$16)") (class "Default")
      (node (ref "U$1") (pin "P$16") (pinfunction "PE13_P$16") (pintype "bidirectional"))
    )
    (net (code "117") (name "unconnected-(U$1A-PE15-PadP$18)") (class "Default")
      (node (ref "U$1") (pin "P$18") (pinfunction "PE15_P$18") (pintype "bidirectional"))
    )
    (net (code "118") (name "unconnected-(U$1B-PA8-PadP$39)") (class "Default")
      (node (ref "U$1") (pin "P$39") (pinfunction "PA8_P$39") (pintype "bidirectional"))
    )
    (net (code "119") (name "unconnected-(U$1B-PA9-PadP$40)") (class "Default")
      (node (ref "U$1") (pin "P$40") (pinfunction "PA9_P$40") (pintype "bidirectional"))
    )
    (net (code "120") (name "unconnected-(U$1B-PB12-PadP$23)") (class "Default")
      (node (ref "U$1") (pin "P$23") (pinfunction "PB12_P$23") (pintype "bidirectional"))
    )
    (net (code "121") (name "unconnected-(U$1B-PB14-PadP$25)") (class "Default")
      (node (ref "U$1") (pin "P$25") (pinfunction "PB14_P$25") (pintype "bidirectional"))
    )
    (net (code "122") (name "unconnected-(U$1B-PC7-PadP$36)") (class "Default")
      (node (ref "U$1") (pin "P$36") (pinfunction "PC7_P$36") (pintype "bidirectional"))
    )
    (net (code "123") (name "unconnected-(U$1B-PC8-PadP$37)") (class "Default")
      (node (ref "U$1") (pin "P$37") (pinfunction "PC8_P$37") (pintype "bidirectional"))
    )
    (net (code "124") (name "unconnected-(U$1B-PC9-PadP$38)") (class "Default")
      (node (ref "U$1") (pin "P$38") (pinfunction "PC9_P$38") (pintype "bidirectional"))
    )
    (net (code "125") (name "unconnected-(U$1B-PD8-PadP$27)") (class "Default")
      (node (ref "U$1") (pin "P$27") (pinfunction "PD8_P$27") (pintype "bidirectional"))
    )
    (net (code "126") (name "unconnected-(U$1B-PD10-PadP$29)") (class "Default")
      (node (ref "U$1") (pin "P$29") (pinfunction "PD10_P$29") (pintype "bidirectional"))
    )
    (net (code "127") (name "unconnected-(U$1B-PD12-PadP$31)") (class "Default")
      (node (ref "U$1") (pin "P$31") (pinfunction "PD12_P$31") (pintype "bidirectional"))
    )
    (net (code "128") (name "unconnected-(U$1B-PD13-PadP$32)") (class "Default")
      (node (ref "U$1") (pin "P$32") (pinfunction "PD13_P$32") (pintype "bidirectional"))
    )
    (net (code "129") (name "unconnected-(U$1B-PD14-PadP$33)") (class "Default")
      (node (ref "U$1") (pin "P$33") (pinfunction "PD14_P$33") (pintype "bidirectional"))
    )
    (net (code "130") (name "unconnected-(U$1B-PD15-PadP$34)") (class "Default")
      (node (ref "U$1") (pin "P$34") (pinfunction "PD15_P$34") (pintype "bidirectional"))
    )
    (net (code "131") (name "unconnected-(U$1C-PB4-PadP$54)") (class "Default")
      (node (ref "U$1") (pin "P$54") (pinfunction "PB4_P$54") (pintype "bidirectional"))
    )
    (net (code "132") (name "unconnected-(U$1C-PB5-PadP$55)") (class "Default")
      (node (ref "U$1") (pin "P$55") (pinfunction "PB5_P$55") (pintype "bidirectional"))
    )
    (net (code "133") (name "unconnected-(U$1C-PB6-PadP$56)") (class "Default")
      (node (ref "U$1") (pin "P$56") (pinfunction "PB6_P$56") (pintype "bidirectional"))
    )
    (net (code "134") (name "unconnected-(U$1C-PB7-PadP$57)") (class "Default")
      (node (ref "U$1") (pin "P$57") (pinfunction "PB7_P$57") (pintype "bidirectional"))
    )
    (net (code "135") (name "unconnected-(U$1C-PB8-PadP$58)") (class "Default")
      (node (ref "U$1") (pin "P$58") (pinfunction "PB8_P$58") (pintype "bidirectional"))
    )
    (net (code "136") (name "unconnected-(U$1C-PB9-PadP$59)") (class "Default")
      (node (ref "U$1") (pin "P$59") (pinfunction "PB9_P$59") (pintype "bidirectional"))
    )
    (net (code "137") (name "unconnected-(U$1C-PC10-PadP$45)") (class "Default")
      (node (ref "U$1") (pin "P$45") (pinfunction "PC10_P$45") (pintype "bidirectional"))
    )
    (net (code "138") (name "unconnected-(U$1C-PC11-PadP$46)") (class "Default")
      (node (ref "U$1") (pin "P$46") (pinfunction "PC11_P$46") (pintype "bidirectional"))
    )
    (net (code "139") (name "unconnected-(U$1C-PC12-PadP$47)") (class "Default")
      (node (ref "U$1") (pin "P$47") (pinfunction "PC12_P$47") (pintype "bidirectional"))
    )
    (net (code "140") (name "unconnected-(U$1C-PD2-PadP$48)") (class "Default")
      (node (ref "U$1") (pin "P$48") (pinfunction "PD2_P$48") (pintype "bidirectional"))
    )
    (net (code "141") (name "unconnected-(U$1C-PD3-PadP$49)") (class "Default")
      (node (ref "U$1") (pin "P$49") (pinfunction "PD3_P$49") (pintype "bidirectional"))
    )
    (net (code "142") (name "unconnected-(U$1C-PD4-PadP$50)") (class "Default")
      (node (ref "U$1") (pin "P$50") (pinfunction "PD4_P$50") (pintype "bidirectional"))
    )
    (net (code "143") (name "unconnected-(U$1C-PD5-PadP$51)") (class "Default")
      (node (ref "U$1") (pin "P$51") (pinfunction "PD5_P$51") (pintype "bidirectional"))
    )
    (net (code "144") (name "unconnected-(U$1C-PD6-PadP$52)") (class "Default")
      (node (ref "U$1") (pin "P$52") (pinfunction "PD6_P$52") (pintype "bidirectional"))
    )
    (net (code "145") (name "unconnected-(U$1C-PD7-PadP$53)") (class "Default")
      (node (ref "U$1") (pin "P$53") (pinfunction "PD7_P$53") (pintype "bidirectional"))
    )
    (net (code "146") (name "unconnected-(U$1C-PE0-PadP$60)") (class "Default")
      (node (ref "U$1") (pin "P$60") (pinfunction "PE0_P$60") (pintype "bidirectional"))
    )
    (net (code "147") (name "unconnected-(U$1C-PE1-PadP$61)") (class "Default")
      (node (ref "U$1") (pin "P$61") (pinfunction "PE1_P$61") (pintype "bidirectional"))
    )
    (net (code "148") (name "unconnected-(U$1D-PA0-PadP$75)") (class "Default")
      (node (ref "U$1") (pin "P$75") (pinfunction "PA0_P$75") (pintype "bidirectional"))
    )
    (net (code "149") (name "unconnected-(U$1D-PA1-PadP$76)") (class "Default")
      (node (ref "U$1") (pin "P$76") (pinfunction "PA1_P$76") (pintype "bidirectional"))
    )
    (net (code "150") (name "unconnected-(U$1D-PA2-PadP$77)") (class "Default")
      (node (ref "U$1") (pin "P$77") (pinfunction "PA2_P$77") (pintype "bidirectional"))
    )
    (net (code "151") (name "unconnected-(U$1D-PC0-PadP$71)") (class "Default")
      (node (ref "U$1") (pin "P$71") (pinfunction "PC0_P$71") (pintype "bidirectional"))
    )
    (net (code "152") (name "unconnected-(U$1D-PC1-PadP$72)") (class "Default")
      (node (ref "U$1") (pin "P$72") (pinfunction "PC1_P$72") (pintype "bidirectional"))
    )
    (net (code "153") (name "unconnected-(U$1D-PC2-PadP$73)") (class "Default")
      (node (ref "U$1") (pin "P$73") (pinfunction "PC2_P$73") (pintype "bidirectional"))
    )
    (net (code "154") (name "unconnected-(U$1D-PC3-PadP$74)") (class "Default")
      (node (ref "U$1") (pin "P$74") (pinfunction "PC3_P$74") (pintype "bidirectional"))
    )
    (net (code "155") (name "unconnected-(U$1D-PC13-PadP$68)") (class "Default")
      (node (ref "U$1") (pin "P$68") (pinfunction "PC13_P$68") (pintype "bidirectional"))
    )
    (net (code "156") (name "unconnected-(U$1D-PE2-PadP$63)") (class "Default")
      (node (ref "U$1") (pin "P$63") (pinfunction "PE2_P$63") (pintype "bidirectional"))
    )
    (net (code "157") (name "unconnected-(U$1D-PE3-PadP$64)") (class "Default")
      (node (ref "U$1") (pin "P$64") (pinfunction "PE3_P$64") (pintype "bidirectional"))
    )
    (net (code "158") (name "unconnected-(U$1D-PE4-PadP$65)") (class "Default")
      (node (ref "U$1") (pin "P$65") (pinfunction "PE4_P$65") (pintype "bidirectional"))
    )
    (net (code "159") (name "unconnected-(U$1D-PE5-PadP$66)") (class "Default")
      (node (ref "U$1") (pin "P$66") (pinfunction "PE5_P$66") (pintype "bidirectional"))
    )
    (net (code "160") (name "unconnected-(U$1D-PE6-PadP$67)") (class "Default")
      (node (ref "U$1") (pin "P$67") (pinfunction "PE6_P$67") (pintype "bidirectional"))
    )
    (net (code "161") (name "unconnected-(U$30-{slash}OUT15-Pad23)") (class "Default")
      (node (ref "U$30") (pin "23") (pinfunction "/OUT15_23") (pintype "bidirectional"))
    )
    (net (code "162") (name "unconnected-(U$33-{slash}OUT15-Pad23)") (class "Default")
      (node (ref "U$33") (pin "23") (pinfunction "/OUT15_23") (pintype "bidirectional"))
    )
    (net (code "163") (name "unconnected-(U$36-{slash}OUT15-Pad23)") (class "Default")
      (node (ref "U$36") (pin "23") (pinfunction "/OUT15_23") (pintype "bidirectional"))
    )
    (net (code "164") (name "unconnected-(U$51-{slash}OUT15-Pad23)") (class "Default")
      (node (ref "U$51") (pin "23") (pinfunction "/OUT15_23") (pintype "bidirectional"))
    )
  )
)
